# FEU31_Part2.net
KiCad netlist of a schematic drawn in Altium Designer
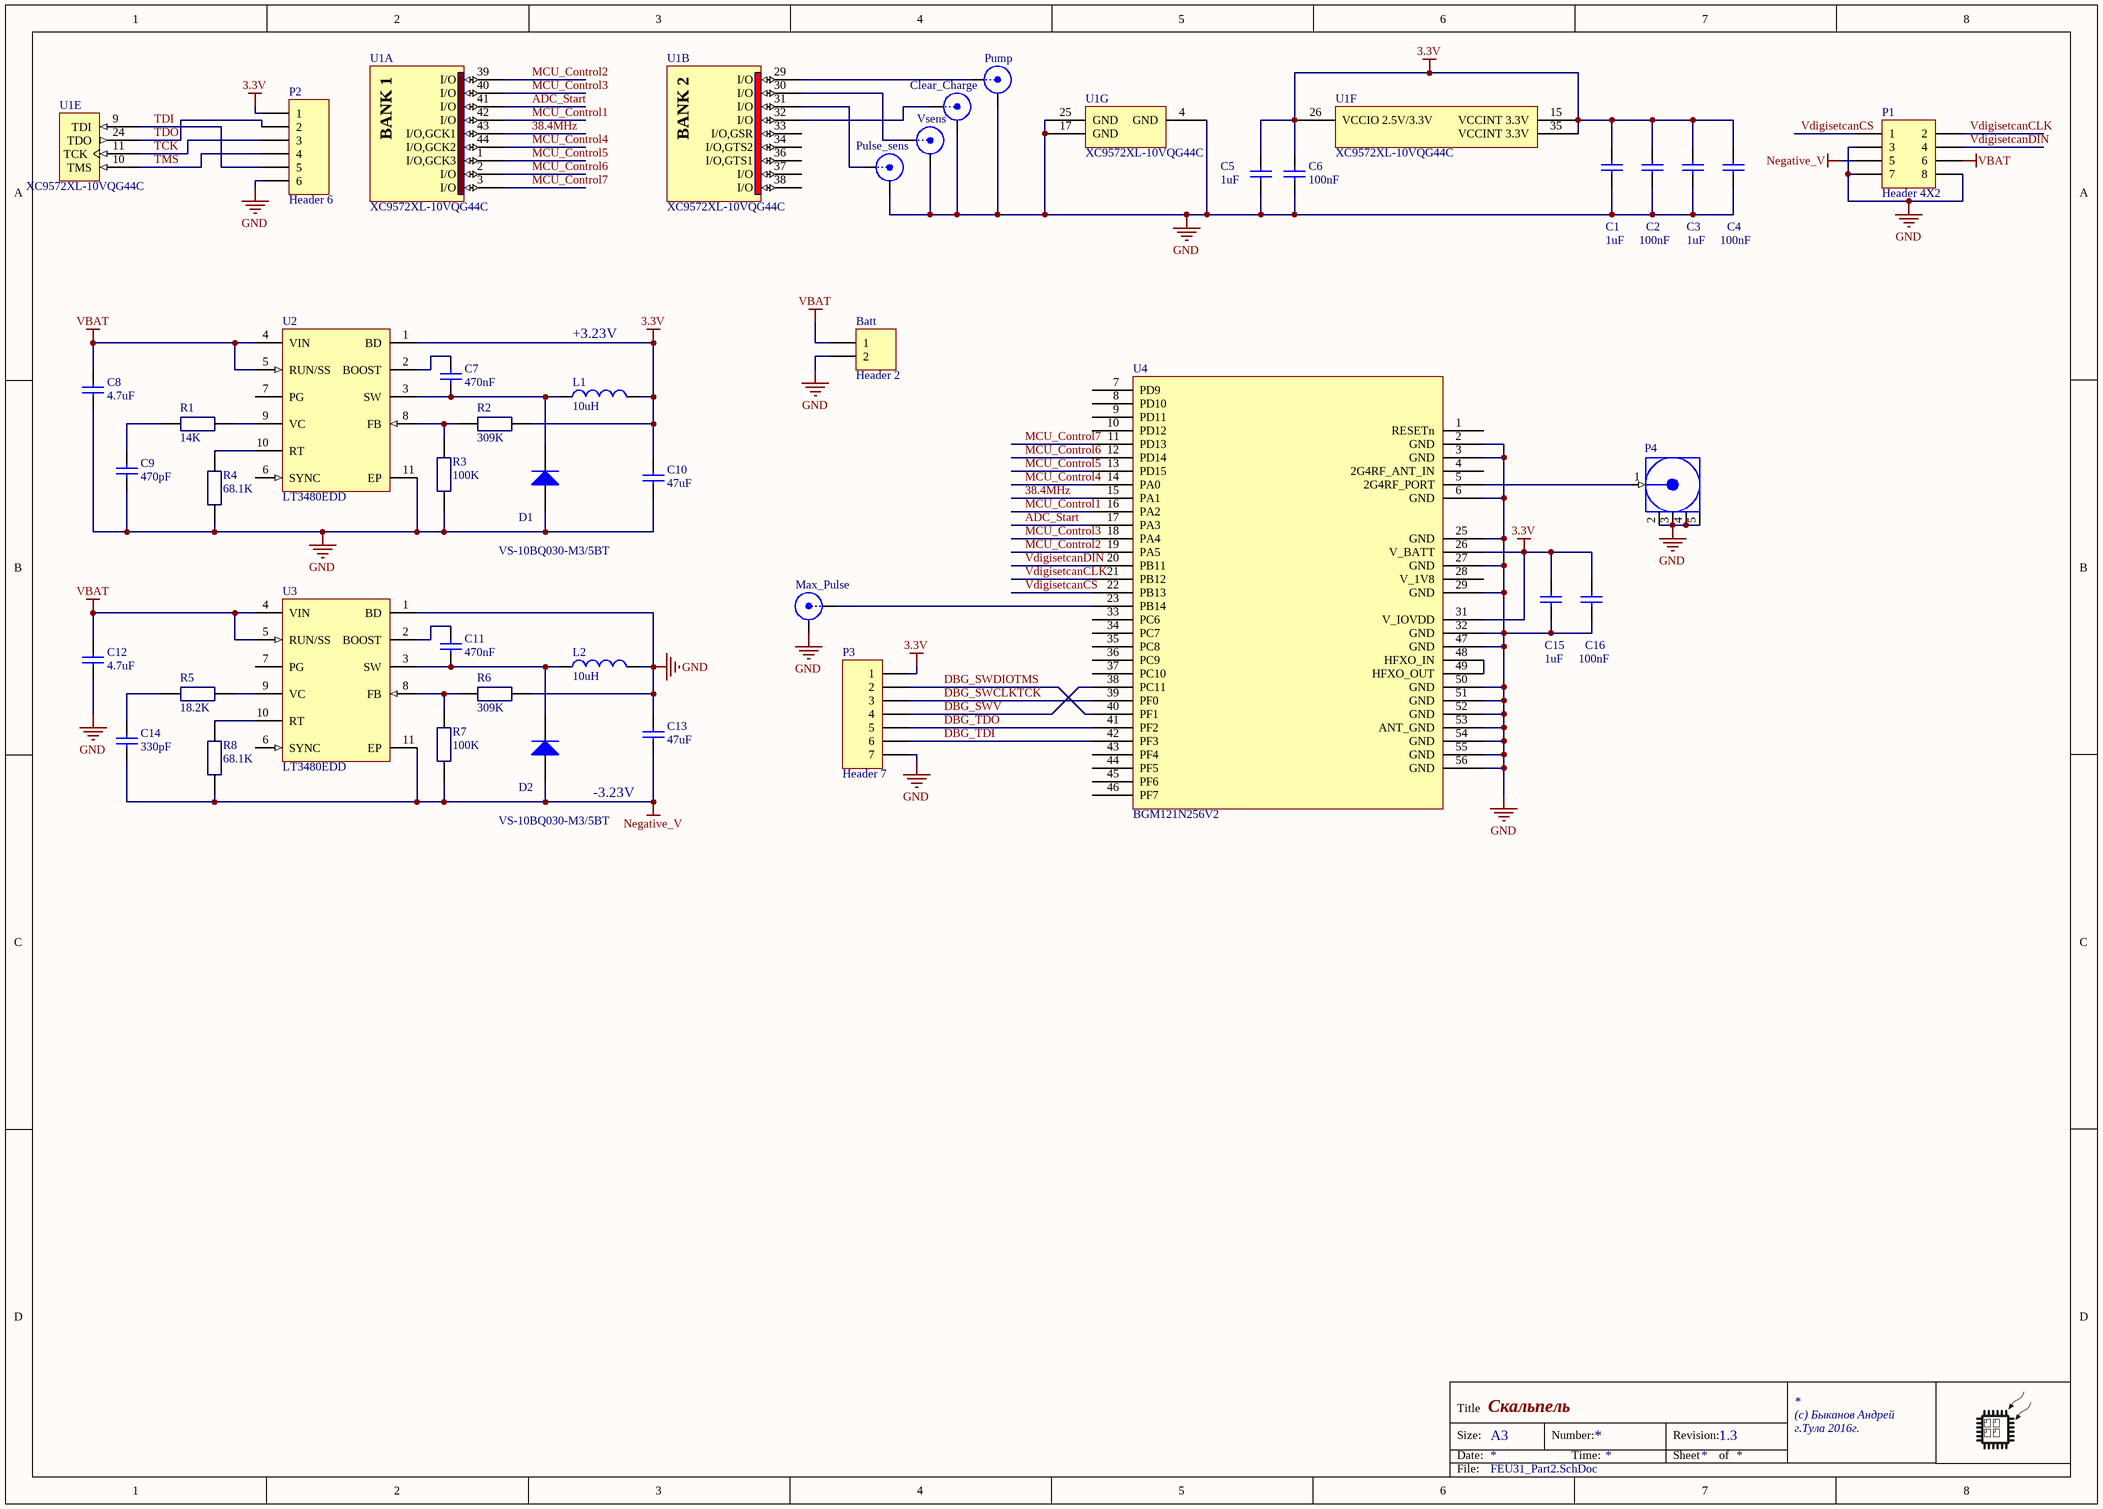
[diagram p0: FEU31_Part2.SchDoc]

(export (version "E")
  (design (tool "Eeschema 10.0.6"))
  (components
    (comp (ref "Batt")
      (value "Header 2")
      (footprint "HDR1X2")
      (description "Header, 2-Pin")
      (fields (field (name "PUBLISHER") "Altium Limited"))
      (libsource (lib "Miscellaneous Connectors") (part "Header 2"))
    )
    (comp (ref "C1")
      (value "1uF")
      (footprint "1608[0603]_CAP")
      (description "Capacitor (Semiconductor SIM Model)")
      (fields (field (name "PUBLISHER") "Altium Limited"))
      (libsource (lib "Miscellaneous Devices") (part "Cap Semi"))
    )
    (comp (ref "C2")
      (value "100nF")
      (footprint "1608[0603]_CAP")
      (description "Capacitor (Semiconductor SIM Model)")
      (fields (field (name "PUBLISHER") "Altium Limited"))
      (libsource (lib "Miscellaneous Devices") (part "Cap Semi"))
    )
    (comp (ref "C3")
      (value "1uF")
      (footprint "1608[0603]_CAP")
      (description "Capacitor (Semiconductor SIM Model)")
      (fields (field (name "PUBLISHER") "Altium Limited"))
      (libsource (lib "Miscellaneous Devices") (part "Cap Semi"))
    )
    (comp (ref "C4")
      (value "100nF")
      (footprint "1608[0603]_CAP")
      (description "Capacitor (Semiconductor SIM Model)")
      (fields (field (name "PUBLISHER") "Altium Limited"))
      (libsource (lib "Miscellaneous Devices") (part "Cap Semi"))
    )
    (comp (ref "C5")
      (value "1uF")
      (footprint "1608[0603]_CAP")
      (description "Capacitor (Semiconductor SIM Model)")
      (fields (field (name "PUBLISHER") "Altium Limited"))
      (libsource (lib "Miscellaneous Devices") (part "Cap Semi"))
    )
    (comp (ref "C6")
      (value "100nF")
      (footprint "1608[0603]_CAP")
      (description "Capacitor (Semiconductor SIM Model)")
      (fields (field (name "PUBLISHER") "Altium Limited"))
      (libsource (lib "Miscellaneous Devices") (part "Cap Semi"))
    )
    (comp (ref "C7")
      (value "470nF")
      (footprint "1608[0603]_CAP")
      (description "Capacitor (Semiconductor SIM Model)")
      (fields (field (name "PUBLISHER") "Altium Limited"))
      (libsource (lib "Miscellaneous Devices") (part "Cap Semi"))
    )
    (comp (ref "C8")
      (value "4.7uF")
      (footprint "C1206")
      (description "Capacitor (Semiconductor SIM Model)")
      (fields (field (name "PUBLISHER") "Altium Limited"))
      (libsource (lib "Miscellaneous Devices") (part "Cap Semi"))
    )
    (comp (ref "C9")
      (value "470pF")
      (footprint "1608[0603]_CAP")
      (description "Capacitor (Semiconductor SIM Model)")
      (fields (field (name "PUBLISHER") "Altium Limited"))
      (libsource (lib "Miscellaneous Devices") (part "Cap Semi"))
    )
    (comp (ref "C10")
      (value "47uF")
      (footprint "C1206")
      (description "Capacitor (Semiconductor SIM Model)")
      (fields (field (name "PUBLISHER") "Altium Limited"))
      (libsource (lib "Miscellaneous Devices") (part "Cap Semi"))
    )
    (comp (ref "C11")
      (value "470nF")
      (footprint "1608[0603]_CAP")
      (description "Capacitor (Semiconductor SIM Model)")
      (fields (field (name "PUBLISHER") "Altium Limited"))
      (libsource (lib "Miscellaneous Devices") (part "Cap Semi"))
    )
    (comp (ref "C12")
      (value "4.7uF")
      (footprint "C1206")
      (description "Capacitor (Semiconductor SIM Model)")
      (fields (field (name "PUBLISHER") "Altium Limited"))
      (libsource (lib "Miscellaneous Devices") (part "Cap Semi"))
    )
    (comp (ref "C13")
      (value "47uF")
      (footprint "C1206")
      (description "Capacitor (Semiconductor SIM Model)")
      (fields (field (name "PUBLISHER") "Altium Limited"))
      (libsource (lib "Miscellaneous Devices") (part "Cap Semi"))
    )
    (comp (ref "C14")
      (value "330pF")
      (footprint "1608[0603]_CAP")
      (description "Capacitor (Semiconductor SIM Model)")
      (fields (field (name "PUBLISHER") "Altium Limited"))
      (libsource (lib "Miscellaneous Devices") (part "Cap Semi"))
    )
    (comp (ref "C15")
      (value "1uF")
      (footprint "1608[0603]_CAP")
      (description "Capacitor (Semiconductor SIM Model)")
      (fields (field (name "PUBLISHER") "Altium Limited"))
      (libsource (lib "Miscellaneous Devices") (part "Cap Semi"))
    )
    (comp (ref "C16")
      (value "100nF")
      (footprint "1608[0603]_CAP")
      (description "Capacitor (Semiconductor SIM Model)")
      (fields (field (name "PUBLISHER") "Altium Limited"))
      (libsource (lib "Miscellaneous Devices") (part "Cap Semi"))
    )
    (comp (ref "Clear_Charge")
      (value "MMCX")
      (footprint "MMCX PCB")
      (description "SMB Straight Connector")
      (fields (field (name "PUBLISHER") "Altium Limited"))
      (libsource (lib "Miscellaneous Connectors") (part "SMB"))
    )
    (comp (ref "D1")
      (value "VS-10BQ030-M3/5BT")
      (footprint "SMB")
      (description "Default Diode")
      (fields (field (name "PUBLISHER") "Altium Limited"))
      (libsource (lib "Miscellaneous Devices") (part "Diode"))
    )
    (comp (ref "D2")
      (value "VS-10BQ030-M3/5BT")
      (footprint "SMB")
      (description "Default Diode")
      (fields (field (name "PUBLISHER") "Altium Limited"))
      (libsource (lib "Miscellaneous Devices") (part "Diode"))
    )
    (comp (ref "L1")
      (value "10uH")
      (footprint "SLF10145")
      (description "Inductor")
      (fields (field (name "PUBLISHER") "Altium Limited"))
      (libsource (lib "Miscellaneous Devices") (part "Inductor"))
    )
    (comp (ref "L2")
      (value "10uH")
      (footprint "SLF10145")
      (description "Inductor")
      (fields (field (name "PUBLISHER") "Altium Limited"))
      (libsource (lib "Miscellaneous Devices") (part "Inductor"))
    )
    (comp (ref "Max_Pulse")
      (value "MMCX")
      (footprint "MMCX PCB")
      (description "SMB Straight Connector")
      (fields (field (name "PUBLISHER") "Altium Limited"))
      (libsource (lib "Miscellaneous Connectors") (part "SMB"))
    )
    (comp (ref "P1")
      (value "Header 4X2")
      (footprint "HDR2X4")
      (description "Header, 4-Pin, Dual row")
      (fields (field (name "PUBLISHER") "Altium Limited"))
      (libsource (lib "Miscellaneous Connectors") (part "Header 4X2"))
    )
    (comp (ref "P2")
      (value "Header 6")
      (footprint "HDR1X6")
      (description "Header, 6-Pin")
      (fields (field (name "PUBLISHER") "Altium Limited"))
      (libsource (lib "Miscellaneous Connectors") (part "Header 6"))
    )
    (comp (ref "P3")
      (value "Header 7")
      (footprint "HDR1X7")
      (description "Header, 7-Pin")
      (fields (field (name "PUBLISHER") "Altium Limited"))
      (libsource (lib "Miscellaneous Connectors") (part "Header 7"))
    )
    (comp (ref "P4")
      (value "COAX-M")
      (footprint "MMCX2.54-V5")
      (description "RF Coaxial PCB Connector, MMCX; Thru-Hole, Vertical Mount Plug,  50 Ohm Impedance")
      (fields (field (name "PUBLISHER") "Altium Limited"))
      (libsource (lib "Miscellaneous Connectors") (part "COAX-M"))
    )
    (comp (ref "Pulse_sens")
      (value "MMCX")
      (footprint "MMCX PCB")
      (description "SMB Straight Connector")
      (fields (field (name "PUBLISHER") "Altium Limited"))
      (libsource (lib "Miscellaneous Connectors") (part "SMB"))
    )
    (comp (ref "Pump")
      (value "MMCX")
      (footprint "MMCX PCB")
      (description "SMB Straight Connector")
      (fields (field (name "PUBLISHER") "Altium Limited"))
      (libsource (lib "Miscellaneous Connectors") (part "SMB"))
    )
    (comp (ref "R1")
      (value "14K")
      (footprint "1608[0603]_RES")
      (libsource (lib "Микрон-3") (part "Resistor 0805"))
    )
    (comp (ref "R2")
      (value "309K")
      (footprint "1608[0603]_RES")
      (libsource (lib "Микрон-3") (part "Resistor 0805"))
    )
    (comp (ref "R3")
      (value "100K")
      (footprint "1608[0603]_RES")
      (libsource (lib "Микрон-3") (part "Resistor 0805"))
    )
    (comp (ref "R4")
      (value "68.1K")
      (footprint "1608[0603]_RES")
      (libsource (lib "Микрон-3") (part "Resistor 0805"))
    )
    (comp (ref "R5")
      (value "18.2K")
      (footprint "1608[0603]_RES")
      (libsource (lib "Микрон-3") (part "Resistor 0805"))
    )
    (comp (ref "R6")
      (value "309K")
      (footprint "1608[0603]_RES")
      (libsource (lib "Микрон-3") (part "Resistor 0805"))
    )
    (comp (ref "R7")
      (value "100K")
      (footprint "1608[0603]_RES")
      (libsource (lib "Микрон-3") (part "Resistor 0805"))
    )
    (comp (ref "R8")
      (value "68.1K")
      (footprint "1608[0603]_RES")
      (libsource (lib "Микрон-3") (part "Resistor 0805"))
    )
    (comp (ref "U1")
      (value "XC9572XL-10VQG44C")
      (footprint "VQG44_N")
      (fields (field (name "PUBLISHER") "Altium Limited"))
      (libsource (lib "Xilinx XC9500XL") (part "XC9572XL-10VQG44C"))
    )
    (comp (ref "U2")
      (value "LT3480EDD")
      (footprint "LT-DD-10_V")
      (fields (field (name "MANUFACTURER") "Linear Technology") (field (name "PARTNUMBER") "LT3480EDD#PBF"))
      (libsource (lib "Linear Technology Power Management Switching Regulator LT1074-LT8705") (part "LT3480EDD#PBF"))
    )
    (comp (ref "U3")
      (value "LT3480EDD")
      (footprint "LT-DD-10_V")
      (fields (field (name "MANUFACTURER") "Linear Technology") (field (name "PARTNUMBER") "LT3480EDD#PBF"))
      (libsource (lib "Linear Technology Power Management Switching Regulator LT1074-LT8705") (part "LT3480EDD#PBF"))
    )
    (comp (ref "U4")
      (value "BGM121N256V2")
      (footprint "BGM121")
      (libsource (lib "My SCH library") (part "BGM121"))
    )
    (comp (ref "Vsens")
      (value "MMCX")
      (footprint "MMCX PCB")
      (description "SMB Straight Connector")
      (fields (field (name "PUBLISHER") "Altium Limited"))
      (libsource (lib "Miscellaneous Connectors") (part "SMB"))
    )
  )
  (nets
    (net (code "1") (name "/38.4MHz") (class "Default")
      (node (ref "U1") (pin "43") (pinfunction "I/O,GCK1_43") (pintype "bidirectional"))
      (node (ref "U4") (pin "15") (pinfunction "PA1_15") (pintype "passive"))
    )
    (net (code "2") (name "/ADC_Start") (class "Default")
      (node (ref "U1") (pin "41") (pinfunction "I/O_41") (pintype "bidirectional"))
      (node (ref "U4") (pin "17") (pinfunction "PA3_17") (pintype "passive"))
    )
    (net (code "3") (name "/DBG_SWCLKTCK") (class "Default")
      (node (ref "P3") (pin "3") (pinfunction "3_3") (pintype "passive"))
      (node (ref "U4") (pin "39") (pinfunction "PF0_39") (pintype "passive"))
    )
    (net (code "4") (name "/DBG_SWDIOTMS") (class "Default")
      (node (ref "P3") (pin "2") (pinfunction "2_2") (pintype "passive"))
      (node (ref "U4") (pin "40") (pinfunction "PF1_40") (pintype "passive"))
    )
    (net (code "5") (name "/DBG_SWV") (class "Default")
      (node (ref "P3") (pin "4") (pinfunction "4_4") (pintype "passive"))
      (node (ref "U4") (pin "38") (pinfunction "PC11_38") (pintype "passive"))
    )
    (net (code "6") (name "/DBG_TDI") (class "Default")
      (node (ref "P3") (pin "6") (pinfunction "6_6") (pintype "passive"))
      (node (ref "U4") (pin "42") (pinfunction "PF3_42") (pintype "passive"))
    )
    (net (code "7") (name "/DBG_TDO") (class "Default")
      (node (ref "P3") (pin "5") (pinfunction "5_5") (pintype "passive"))
      (node (ref "U4") (pin "41") (pinfunction "PF2_41") (pintype "passive"))
    )
    (net (code "8") (name "/MCU_Control1") (class "Default")
      (node (ref "U1") (pin "42") (pinfunction "I/O_42") (pintype "bidirectional"))
      (node (ref "U4") (pin "16") (pinfunction "PA2_16") (pintype "passive"))
    )
    (net (code "9") (name "/MCU_Control2") (class "Default")
      (node (ref "U1") (pin "39") (pinfunction "I/O_39") (pintype "bidirectional"))
      (node (ref "U4") (pin "19") (pinfunction "PA5_19") (pintype "passive"))
    )
    (net (code "10") (name "/MCU_Control3") (class "Default")
      (node (ref "U1") (pin "40") (pinfunction "I/O_40") (pintype "bidirectional"))
      (node (ref "U4") (pin "18") (pinfunction "PA4_18") (pintype "passive"))
    )
    (net (code "11") (name "/MCU_Control4") (class "Default")
      (node (ref "U1") (pin "44") (pinfunction "I/O,GCK2_44") (pintype "bidirectional"))
      (node (ref "U4") (pin "14") (pinfunction "PA0_14") (pintype "passive"))
    )
    (net (code "12") (name "/MCU_Control5") (class "Default")
      (node (ref "U1") (pin "1") (pinfunction "I/O,GCK3_1") (pintype "bidirectional"))
      (node (ref "U4") (pin "13") (pinfunction "PD15_13") (pintype "passive"))
    )
    (net (code "13") (name "/MCU_Control6") (class "Default")
      (node (ref "U1") (pin "2") (pinfunction "I/O_2") (pintype "bidirectional"))
      (node (ref "U4") (pin "12") (pinfunction "PD14_12") (pintype "passive"))
    )
    (net (code "14") (name "/MCU_Control7") (class "Default")
      (node (ref "U1") (pin "3") (pinfunction "I/O_3") (pintype "bidirectional"))
      (node (ref "U4") (pin "11") (pinfunction "PD13_11") (pintype "passive"))
    )
    (net (code "15") (name "/TCK") (class "Default")
      (node (ref "P2") (pin "3") (pinfunction "3_3") (pintype "passive"))
      (node (ref "U1") (pin "11") (pinfunction "TCK_11") (pintype "input"))
    )
    (net (code "16") (name "/TDI") (class "Default")
      (node (ref "P2") (pin "5") (pinfunction "5_5") (pintype "passive"))
      (node (ref "U1") (pin "9") (pinfunction "TDI_9") (pintype "input"))
    )
    (net (code "17") (name "/TDO") (class "Default")
      (node (ref "P2") (pin "2") (pinfunction "2_2") (pintype "passive"))
      (node (ref "U1") (pin "24") (pinfunction "TDO_24") (pintype "output"))
    )
    (net (code "18") (name "/TMS") (class "Default")
      (node (ref "P2") (pin "4") (pinfunction "4_4") (pintype "passive"))
      (node (ref "U1") (pin "10") (pinfunction "TMS_10") (pintype "input"))
    )
    (net (code "19") (name "/VdigisetcanCLK") (class "Default")
      (node (ref "P1") (pin "2") (pinfunction "2_2") (pintype "passive"))
      (node (ref "U4") (pin "21") (pinfunction "PB12_21") (pintype "passive"))
    )
    (net (code "20") (name "/VdigisetcanCS") (class "Default")
      (node (ref "P1") (pin "1") (pinfunction "1_1") (pintype "passive"))
      (node (ref "U4") (pin "22") (pinfunction "PB13_22") (pintype "passive"))
    )
    (net (code "21") (name "/VdigisetcanDIN") (class "Default")
      (node (ref "P1") (pin "4") (pinfunction "4_4") (pintype "passive"))
      (node (ref "U4") (pin "20") (pinfunction "PB11_20") (pintype "passive"))
    )
    (net (code "22") (name "3.3V") (class "Default")
      (node (ref "C1") (pin "1") (pinfunction "1_1") (pintype "passive"))
      (node (ref "C10") (pin "1") (pinfunction "1_1") (pintype "passive"))
      (node (ref "C15") (pin "1") (pinfunction "1_1") (pintype "passive"))
      (node (ref "C16") (pin "1") (pinfunction "1_1") (pintype "passive"))
      (node (ref "C2") (pin "1") (pinfunction "1_1") (pintype "passive"))
      (node (ref "C3") (pin "1") (pinfunction "1_1") (pintype "passive"))
      (node (ref "C4") (pin "1") (pinfunction "1_1") (pintype "passive"))
      (node (ref "C5") (pin "1") (pinfunction "1_1") (pintype "passive"))
      (node (ref "C6") (pin "1") (pinfunction "1_1") (pintype "passive"))
      (node (ref "L1") (pin "2") (pinfunction "2_2") (pintype "passive"))
      (node (ref "P2") (pin "1") (pinfunction "1_1") (pintype "passive"))
      (node (ref "P3") (pin "1") (pinfunction "1_1") (pintype "passive"))
      (node (ref "R2") (pin "2") (pinfunction "2_2") (pintype "passive"))
      (node (ref "U1") (pin "15") (pinfunction "VCCINT_3.3V_15") (pintype "power_in"))
      (node (ref "U1") (pin "26") (pinfunction "VCCIO_2.5V/3.3V_26") (pintype "power_in"))
      (node (ref "U1") (pin "35") (pinfunction "VCCINT_3.3V_35") (pintype "power_in"))
      (node (ref "U2") (pin "1") (pinfunction "BD_1") (pintype "power_in"))
      (node (ref "U4") (pin "26") (pinfunction "V_BATT_26") (pintype "passive"))
      (node (ref "U4") (pin "31") (pinfunction "V_IOVDD_31") (pintype "passive"))
    )
    (net (code "23") (name "GND") (class "Default")
      (node (ref "Batt") (pin "2") (pinfunction "2_2") (pintype "passive"))
      (node (ref "C1") (pin "2") (pinfunction "2_2") (pintype "passive"))
      (node (ref "C10") (pin "2") (pinfunction "2_2") (pintype "passive"))
      (node (ref "C12") (pin "2") (pinfunction "2_2") (pintype "passive"))
      (node (ref "C13") (pin "1") (pinfunction "1_1") (pintype "passive"))
      (node (ref "C15") (pin "2") (pinfunction "2_2") (pintype "passive"))
      (node (ref "C16") (pin "2") (pinfunction "2_2") (pintype "passive"))
      (node (ref "C2") (pin "2") (pinfunction "2_2") (pintype "passive"))
      (node (ref "C3") (pin "2") (pinfunction "2_2") (pintype "passive"))
      (node (ref "C4") (pin "2") (pinfunction "2_2") (pintype "passive"))
      (node (ref "C5") (pin "2") (pinfunction "2_2") (pintype "passive"))
      (node (ref "C6") (pin "2") (pinfunction "2_2") (pintype "passive"))
      (node (ref "C8") (pin "2") (pinfunction "2_2") (pintype "passive"))
      (node (ref "C9") (pin "2") (pinfunction "2_2") (pintype "passive"))
      (node (ref "Clear_Charge") (pin "2") (pinfunction "Y_2") (pintype "passive"))
      (node (ref "D1") (pin "1") (pinfunction "A_1") (pintype "passive"))
      (node (ref "L2") (pin "2") (pinfunction "2_2") (pintype "passive"))
      (node (ref "Max_Pulse") (pin "2") (pinfunction "Y_2") (pintype "passive"))
      (node (ref "P1") (pin "3") (pinfunction "3_3") (pintype "passive"))
      (node (ref "P1") (pin "7") (pinfunction "7_7") (pintype "passive"))
      (node (ref "P1") (pin "8") (pinfunction "8_8") (pintype "passive"))
      (node (ref "P2") (pin "6") (pinfunction "6_6") (pintype "passive"))
      (node (ref "P3") (pin "7") (pinfunction "7_7") (pintype "passive"))
      (node (ref "P4") (pin "2") (pinfunction "GND_2") (pintype "power_in"))
      (node (ref "P4") (pin "3") (pinfunction "GND_3") (pintype "power_in"))
      (node (ref "P4") (pin "4") (pinfunction "GND_4") (pintype "power_in"))
      (node (ref "P4") (pin "5") (pinfunction "GND_5") (pintype "power_in"))
      (node (ref "Pulse_sens") (pin "2") (pinfunction "Y_2") (pintype "passive"))
      (node (ref "Pump") (pin "2") (pinfunction "Y_2") (pintype "passive"))
      (node (ref "R3") (pin "1") (pinfunction "A_1") (pintype "passive"))
      (node (ref "R4") (pin "1") (pinfunction "A_1") (pintype "passive"))
      (node (ref "R6") (pin "2") (pinfunction "2_2") (pintype "passive"))
      (node (ref "U1") (pin "17") (pinfunction "GND_17") (pintype "power_in"))
      (node (ref "U1") (pin "25") (pinfunction "GND_25") (pintype "power_in"))
      (node (ref "U1") (pin "4") (pinfunction "GND_4") (pintype "power_in"))
      (node (ref "U2") (pin "11") (pinfunction "EP_11") (pintype "power_in"))
      (node (ref "U3") (pin "1") (pinfunction "BD_1") (pintype "power_in"))
      (node (ref "U4") (pin "2") (pinfunction "GND_2") (pintype "passive"))
      (node (ref "U4") (pin "25") (pinfunction "GND_25") (pintype "passive"))
      (node (ref "U4") (pin "27") (pinfunction "GND_27") (pintype "passive"))
      (node (ref "U4") (pin "29") (pinfunction "GND_29") (pintype "passive"))
      (node (ref "U4") (pin "3") (pinfunction "GND_3") (pintype "passive"))
      (node (ref "U4") (pin "32") (pinfunction "GND_32") (pintype "passive"))
      (node (ref "U4") (pin "47") (pinfunction "GND_47") (pintype "passive"))
      (node (ref "U4") (pin "50") (pinfunction "GND_50") (pintype "passive"))
      (node (ref "U4") (pin "51") (pinfunction "GND_51") (pintype "passive"))
      (node (ref "U4") (pin "52") (pinfunction "GND_52") (pintype "passive"))
      (node (ref "U4") (pin "53") (pinfunction "ANT_GND_53") (pintype "passive"))
      (node (ref "U4") (pin "54") (pinfunction "GND_54") (pintype "passive"))
      (node (ref "U4") (pin "55") (pinfunction "GND_55") (pintype "passive"))
      (node (ref "U4") (pin "56") (pinfunction "GND_56") (pintype "passive"))
      (node (ref "U4") (pin "6") (pinfunction "GND_6") (pintype "passive"))
      (node (ref "Vsens") (pin "2") (pinfunction "Y_2") (pintype "passive"))
    )
    (net (code "24") (name "Negative_V") (class "Default")
      (node (ref "C13") (pin "2") (pinfunction "2_2") (pintype "passive"))
      (node (ref "C14") (pin "2") (pinfunction "2_2") (pintype "passive"))
      (node (ref "D2") (pin "1") (pinfunction "A_1") (pintype "passive"))
      (node (ref "P1") (pin "5") (pinfunction "5_5") (pintype "passive"))
      (node (ref "R7") (pin "1") (pinfunction "A_1") (pintype "passive"))
      (node (ref "R8") (pin "1") (pinfunction "A_1") (pintype "passive"))
      (node (ref "U3") (pin "11") (pinfunction "EP_11") (pintype "power_in"))
    )
    (net (code "25") (name "Net-(Clear_Charge-X)") (class "Default")
      (node (ref "Clear_Charge") (pin "1") (pinfunction "X_1") (pintype "passive"))
      (node (ref "U1") (pin "32") (pinfunction "I/O_32") (pintype "bidirectional"))
    )
    (net (code "26") (name "Net-(D1-K)") (class "Default")
      (node (ref "C7") (pin "2") (pinfunction "2_2") (pintype "passive"))
      (node (ref "D1") (pin "2") (pinfunction "K_2") (pintype "passive"))
      (node (ref "L1") (pin "1") (pinfunction "1_1") (pintype "passive"))
      (node (ref "U2") (pin "3") (pinfunction "SW_3") (pintype "power_in"))
    )
    (net (code "27") (name "Net-(D2-K)") (class "Default")
      (node (ref "C11") (pin "2") (pinfunction "2_2") (pintype "passive"))
      (node (ref "D2") (pin "2") (pinfunction "K_2") (pintype "passive"))
      (node (ref "L2") (pin "1") (pinfunction "1_1") (pintype "passive"))
      (node (ref "U3") (pin "3") (pinfunction "SW_3") (pintype "power_in"))
    )
    (net (code "28") (name "Net-(Max_Pulse-X)") (class "Default")
      (node (ref "Max_Pulse") (pin "1") (pinfunction "X_1") (pintype "passive"))
      (node (ref "U4") (pin "23") (pinfunction "PB14_23") (pintype "passive"))
    )
    (net (code "29") (name "Net-(P4-Signal)") (class "Default")
      (node (ref "P4") (pin "1") (pinfunction "Signal_1") (pintype "input"))
      (node (ref "U4") (pin "5") (pinfunction "2G4RF_PORT_5") (pintype "passive"))
    )
    (net (code "30") (name "Net-(Pulse_sens-X)") (class "Default")
      (node (ref "Pulse_sens") (pin "1") (pinfunction "X_1") (pintype "passive"))
      (node (ref "U1") (pin "31") (pinfunction "I/O_31") (pintype "bidirectional"))
    )
    (net (code "31") (name "Net-(Pump-X)") (class "Default")
      (node (ref "Pump") (pin "1") (pinfunction "X_1") (pintype "passive"))
      (node (ref "U1") (pin "29") (pinfunction "I/O_29") (pintype "bidirectional"))
    )
    (net (code "32") (name "Net-(R1-A)") (class "Default")
      (node (ref "C9") (pin "1") (pinfunction "1_1") (pintype "passive"))
      (node (ref "R1") (pin "1") (pinfunction "A_1") (pintype "passive"))
    )
    (net (code "33") (name "Net-(R2-A)") (class "Default")
      (node (ref "R2") (pin "1") (pinfunction "A_1") (pintype "passive"))
      (node (ref "R3") (pin "2") (pinfunction "2_2") (pintype "passive"))
      (node (ref "U2") (pin "8") (pinfunction "FB_8") (pintype "input"))
    )
    (net (code "34") (name "Net-(R5-A)") (class "Default")
      (node (ref "C14") (pin "1") (pinfunction "1_1") (pintype "passive"))
      (node (ref "R5") (pin "1") (pinfunction "A_1") (pintype "passive"))
    )
    (net (code "35") (name "Net-(R6-A)") (class "Default")
      (node (ref "R6") (pin "1") (pinfunction "A_1") (pintype "passive"))
      (node (ref "R7") (pin "2") (pinfunction "2_2") (pintype "passive"))
      (node (ref "U3") (pin "8") (pinfunction "FB_8") (pintype "input"))
    )
    (net (code "36") (name "Net-(U2-BOOST)") (class "Default")
      (node (ref "C7") (pin "1") (pinfunction "1_1") (pintype "passive"))
      (node (ref "U2") (pin "2") (pinfunction "BOOST_2") (pintype "passive"))
    )
    (net (code "37") (name "Net-(U2-RT)") (class "Default")
      (node (ref "R4") (pin "2") (pinfunction "2_2") (pintype "passive"))
      (node (ref "U2") (pin "10") (pinfunction "RT_10") (pintype "passive"))
    )
    (net (code "38") (name "Net-(U2-VC)") (class "Default")
      (node (ref "R1") (pin "2") (pinfunction "2_2") (pintype "passive"))
      (node (ref "U2") (pin "9") (pinfunction "VC_9") (pintype "passive"))
    )
    (net (code "39") (name "Net-(U3-BOOST)") (class "Default")
      (node (ref "C11") (pin "1") (pinfunction "1_1") (pintype "passive"))
      (node (ref "U3") (pin "2") (pinfunction "BOOST_2") (pintype "passive"))
    )
    (net (code "40") (name "Net-(U3-RT)") (class "Default")
      (node (ref "R8") (pin "2") (pinfunction "2_2") (pintype "passive"))
      (node (ref "U3") (pin "10") (pinfunction "RT_10") (pintype "passive"))
    )
    (net (code "41") (name "Net-(U3-VC)") (class "Default")
      (node (ref "R5") (pin "2") (pinfunction "2_2") (pintype "passive"))
      (node (ref "U3") (pin "9") (pinfunction "VC_9") (pintype "passive"))
    )
    (net (code "42") (name "Net-(U4-HFXO_IN)") (class "Default")
      (node (ref "U4") (pin "48") (pinfunction "HFXO_IN_48") (pintype "passive"))
      (node (ref "U4") (pin "49") (pinfunction "HFXO_OUT_49") (pintype "passive"))
    )
    (net (code "43") (name "Net-(Vsens-X)") (class "Default")
      (node (ref "U1") (pin "30") (pinfunction "I/O_30") (pintype "bidirectional"))
      (node (ref "Vsens") (pin "1") (pinfunction "X_1") (pintype "passive"))
    )
    (net (code "44") (name "VBAT") (class "Default")
      (node (ref "Batt") (pin "1") (pinfunction "1_1") (pintype "passive"))
      (node (ref "C12") (pin "1") (pinfunction "1_1") (pintype "passive"))
      (node (ref "C8") (pin "1") (pinfunction "1_1") (pintype "passive"))
      (node (ref "P1") (pin "6") (pinfunction "6_6") (pintype "passive"))
      (node (ref "U2") (pin "4") (pinfunction "VIN_4") (pintype "power_in"))
      (node (ref "U2") (pin "5") (pinfunction "RUN/SS_5") (pintype "input"))
      (node (ref "U3") (pin "4") (pinfunction "VIN_4") (pintype "power_in"))
      (node (ref "U3") (pin "5") (pinfunction "RUN/SS_5") (pintype "input"))
    )
    (net (code "45") (name "unconnected-(U1B-I{slash}O,GSR-Pad33)") (class "Default")
      (node (ref "U1") (pin "33") (pinfunction "I/O,GSR_33") (pintype "bidirectional"))
    )
    (net (code "46") (name "unconnected-(U1B-I{slash}O,GTS1-Pad36)") (class "Default")
      (node (ref "U1") (pin "36") (pinfunction "I/O,GTS1_36") (pintype "bidirectional"))
    )
    (net (code "47") (name "unconnected-(U1B-I{slash}O,GTS2-Pad34)") (class "Default")
      (node (ref "U1") (pin "34") (pinfunction "I/O,GTS2_34") (pintype "bidirectional"))
    )
    (net (code "48") (name "unconnected-(U1B-I{slash}O-Pad37)") (class "Default")
      (node (ref "U1") (pin "37") (pinfunction "I/O_37") (pintype "bidirectional"))
    )
    (net (code "49") (name "unconnected-(U1B-I{slash}O-Pad38)") (class "Default")
      (node (ref "U1") (pin "38") (pinfunction "I/O_38") (pintype "bidirectional"))
    )
    (net (code "50") (name "unconnected-(U2-PG-Pad7)") (class "Default")
      (node (ref "U2") (pin "7") (pinfunction "PG_7") (pintype "open_collector"))
    )
    (net (code "51") (name "unconnected-(U2-SYNC-Pad6)") (class "Default")
      (node (ref "U2") (pin "6") (pinfunction "SYNC_6") (pintype "input"))
    )
    (net (code "52") (name "unconnected-(U3-PG-Pad7)") (class "Default")
      (node (ref "U3") (pin "7") (pinfunction "PG_7") (pintype "open_collector"))
    )
    (net (code "53") (name "unconnected-(U3-SYNC-Pad6)") (class "Default")
      (node (ref "U3") (pin "6") (pinfunction "SYNC_6") (pintype "input"))
    )
    (net (code "54") (name "unconnected-(U4-2G4RF_ANT_IN-Pad4)") (class "Default")
      (node (ref "U4") (pin "4") (pinfunction "2G4RF_ANT_IN_4") (pintype "passive"))
    )
    (net (code "55") (name "unconnected-(U4-PC6-Pad33)") (class "Default")
      (node (ref "U4") (pin "33") (pinfunction "PC6_33") (pintype "passive"))
    )
    (net (code "56") (name "unconnected-(U4-PC7-Pad34)") (class "Default")
      (node (ref "U4") (pin "34") (pinfunction "PC7_34") (pintype "passive"))
    )
    (net (code "57") (name "unconnected-(U4-PC8-Pad35)") (class "Default")
      (node (ref "U4") (pin "35") (pinfunction "PC8_35") (pintype "passive"))
    )
    (net (code "58") (name "unconnected-(U4-PC9-Pad36)") (class "Default")
      (node (ref "U4") (pin "36") (pinfunction "PC9_36") (pintype "passive"))
    )
    (net (code "59") (name "unconnected-(U4-PC10-Pad37)") (class "Default")
      (node (ref "U4") (pin "37") (pinfunction "PC10_37") (pintype "passive"))
    )
    (net (code "60") (name "unconnected-(U4-PD9-Pad7)") (class "Default")
      (node (ref "U4") (pin "7") (pinfunction "PD9_7") (pintype "passive"))
    )
    (net (code "61") (name "unconnected-(U4-PD10-Pad8)") (class "Default")
      (node (ref "U4") (pin "8") (pinfunction "PD10_8") (pintype "passive"))
    )
    (net (code "62") (name "unconnected-(U4-PD11-Pad9)") (class "Default")
      (node (ref "U4") (pin "9") (pinfunction "PD11_9") (pintype "passive"))
    )
    (net (code "63") (name "unconnected-(U4-PD12-Pad10)") (class "Default")
      (node (ref "U4") (pin "10") (pinfunction "PD12_10") (pintype "passive"))
    )
    (net (code "64") (name "unconnected-(U4-PF4-Pad43)") (class "Default")
      (node (ref "U4") (pin "43") (pinfunction "PF4_43") (pintype "passive"))
    )
    (net (code "65") (name "unconnected-(U4-PF5-Pad44)") (class "Default")
      (node (ref "U4") (pin "44") (pinfunction "PF5_44") (pintype "passive"))
    )
    (net (code "66") (name "unconnected-(U4-PF6-Pad45)") (class "Default")
      (node (ref "U4") (pin "45") (pinfunction "PF6_45") (pintype "passive"))
    )
    (net (code "67") (name "unconnected-(U4-PF7-Pad46)") (class "Default")
      (node (ref "U4") (pin "46") (pinfunction "PF7_46") (pintype "passive"))
    )
    (net (code "68") (name "unconnected-(U4-RESETn-Pad1)") (class "Default")
      (node (ref "U4") (pin "1") (pinfunction "RESETn_1") (pintype "passive"))
    )
    (net (code "69") (name "unconnected-(U4-V_1V8-Pad28)") (class "Default")
      (node (ref "U4") (pin "28") (pinfunction "V_1V8_28") (pintype "passive"))
    )
  )
)
